# SCH_StairLights_2023-04-26.net
KiCad netlist of a schematic drawn in EasyEDA
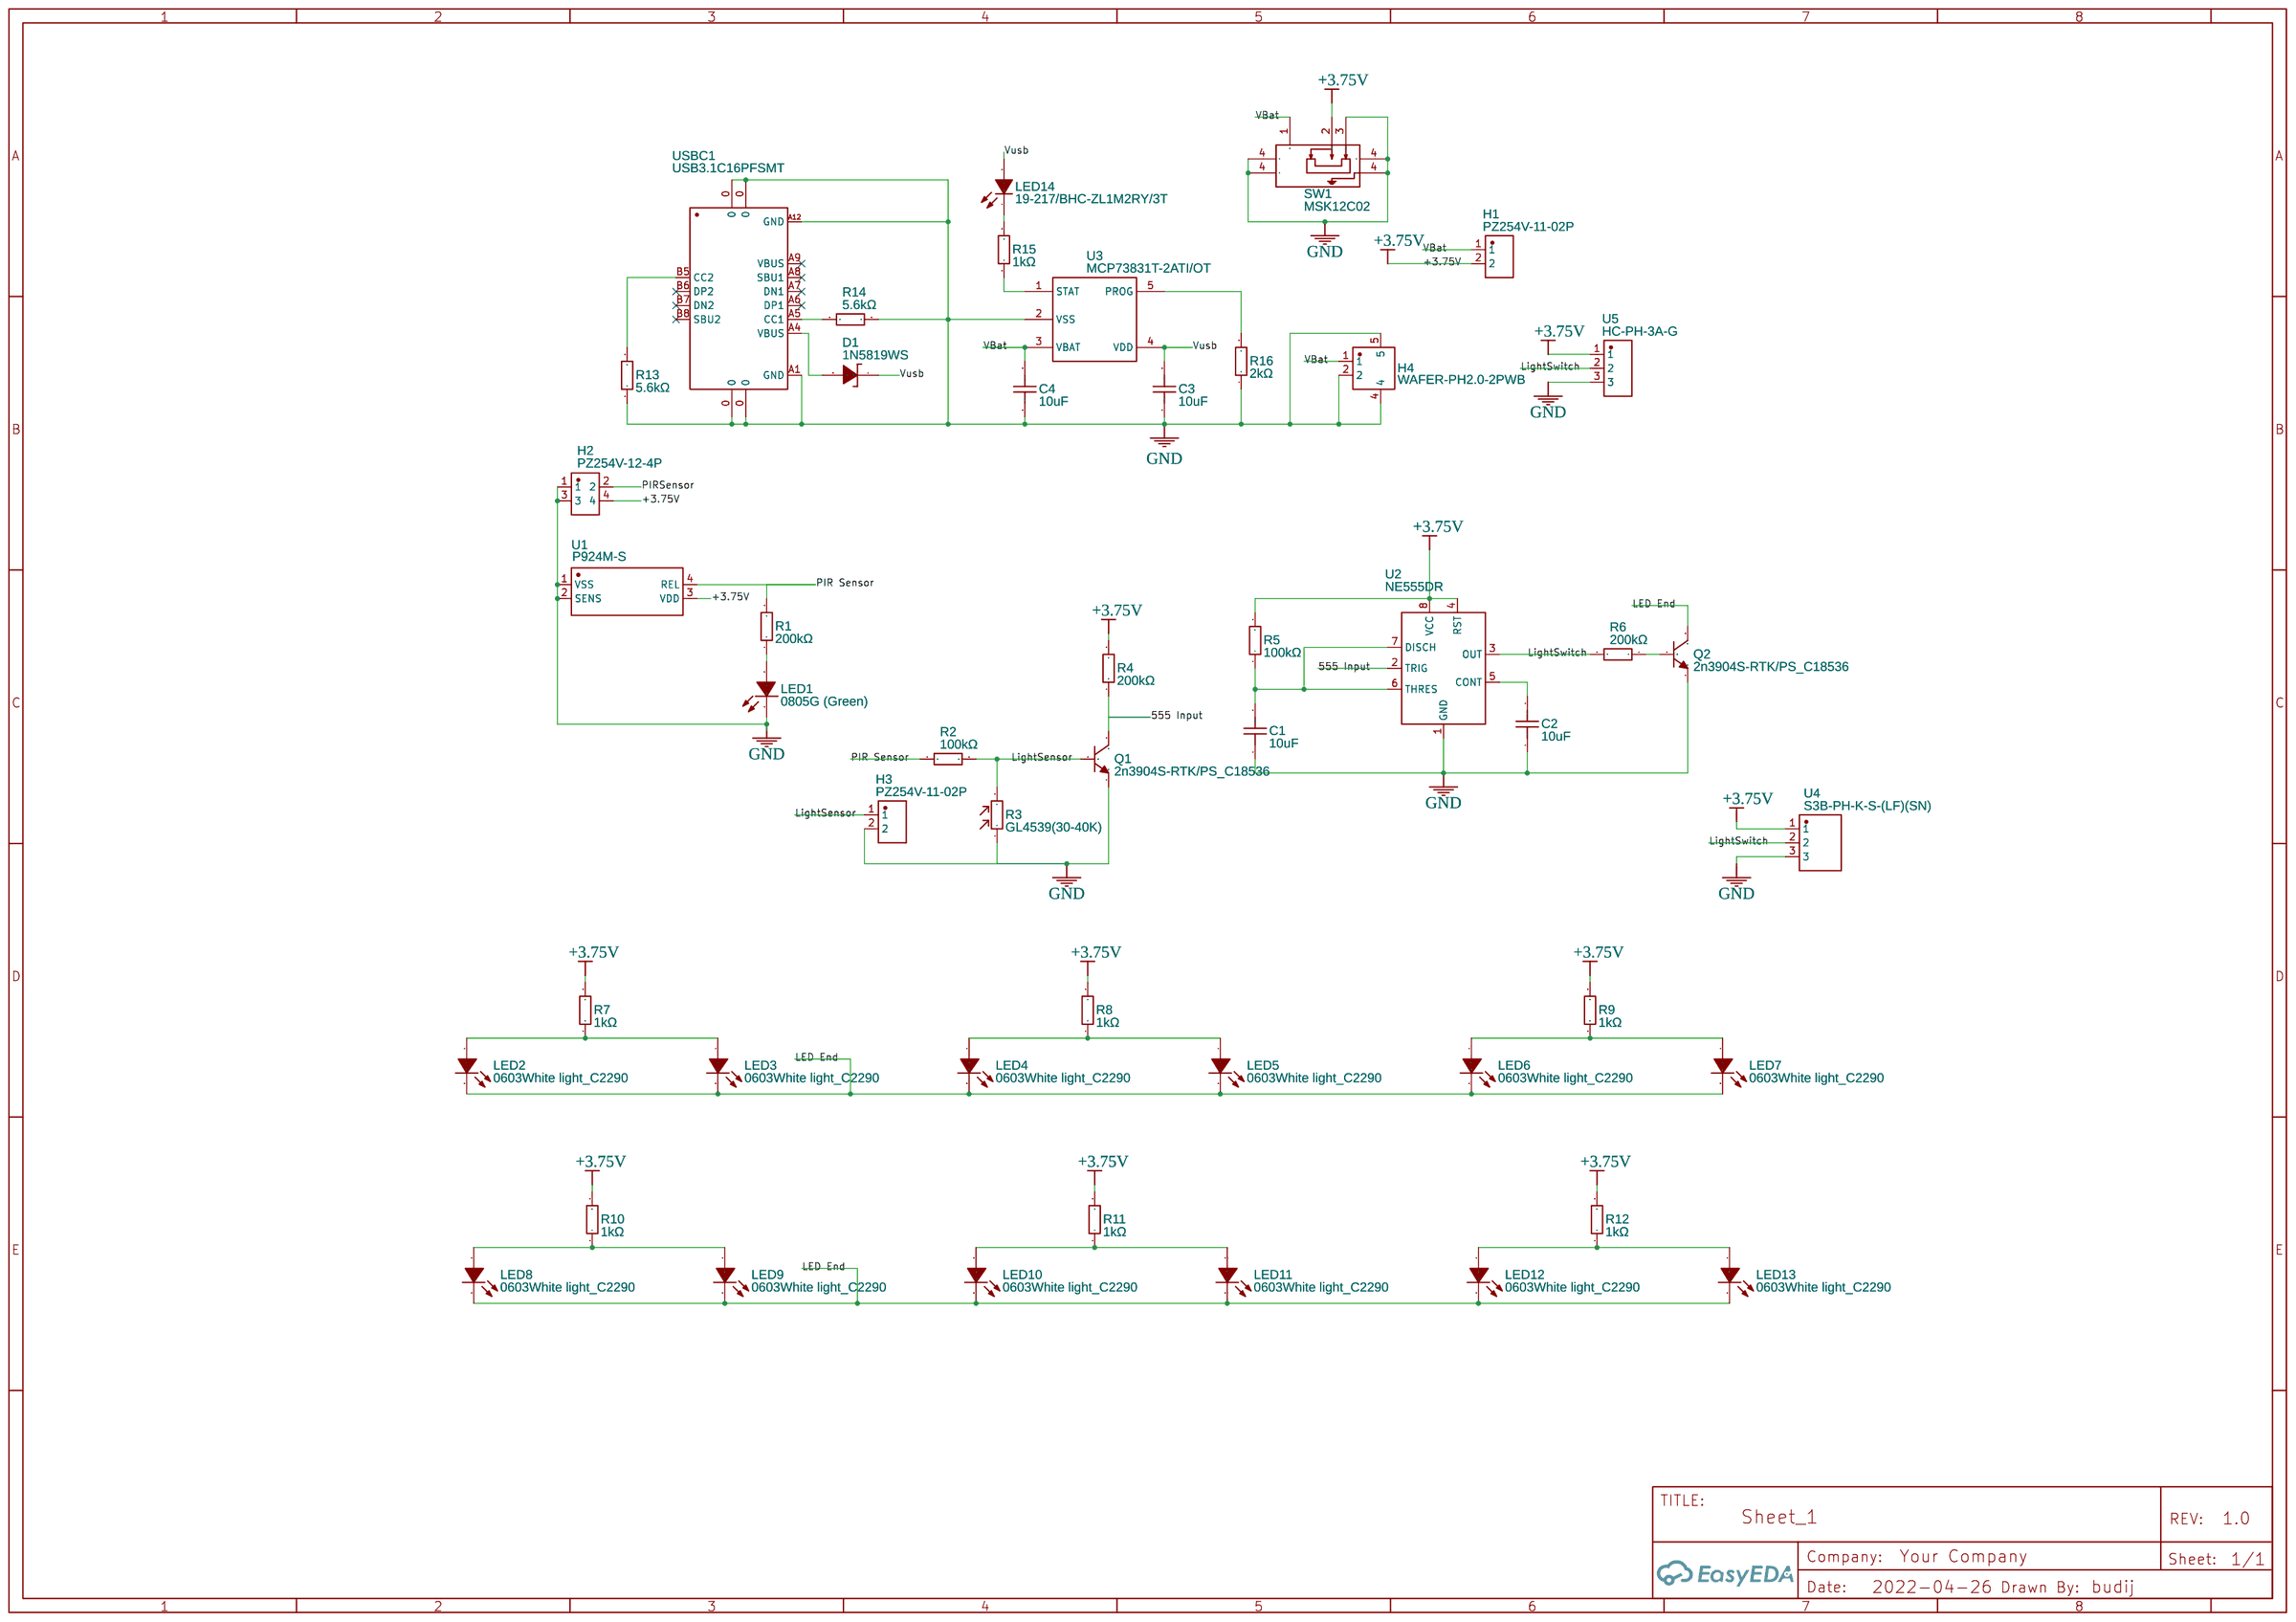
[diagram p0: schematic sheet]

(export (version "E")
  (design (tool "Eeschema 10.0.6"))
  (components
    (comp (ref "C1")
      (value "10uF")
      (fields
        (field (name "BOM_Manufacturer Part") "CL10A106KP8NNNC")
        (field (name "BOM_Supplier Part") "C19702")
      )
      (libsource (lib "") (part "CL10A106KP8NNNC"))
    )
    (comp (ref "C2")
      (value "10uF")
      (fields
        (field (name "BOM_Manufacturer Part") "CL10A106KP8NNNC")
        (field (name "BOM_Supplier Part") "C19702")
      )
      (libsource (lib "") (part "CL10A106KP8NNNC"))
    )
    (comp (ref "C3")
      (value "10uF")
      (fields
        (field (name "BOM_Manufacturer Part") "CL10A106KP8NNNC")
        (field (name "BOM_Supplier Part") "C19702")
      )
      (libsource (lib "") (part "CL10A106KP8NNNC"))
    )
    (comp (ref "C4")
      (value "10uF")
      (fields
        (field (name "BOM_Manufacturer Part") "CL10A106KP8NNNC")
        (field (name "BOM_Supplier Part") "C19702")
      )
      (libsource (lib "") (part "CL10A106KP8NNNC"))
    )
    (comp (ref "D1")
      (value "1N5819WS")
      (fields (field (name "BOM_Supplier Part") "C191023"))
      (libsource (lib "") (part "1N5819WS"))
    )
    (comp (ref "H1")
      (value "PZ254V-11-02P")
      (fields (field (name "BOM_Supplier Part") "C492401"))
      (libsource (lib "") (part "PZ254V-11-02P"))
    )
    (comp (ref "H2")
      (value "PZ254V-12-4P")
      (fields (field (name "BOM_Supplier Part") "C492419"))
      (libsource (lib "") (part "PZ254V-12-4P"))
    )
    (comp (ref "H3")
      (value "PZ254V-11-02P")
      (fields (field (name "BOM_Supplier Part") "C492401"))
      (libsource (lib "") (part "PZ254V-11-02P"))
    )
    (comp (ref "H4")
      (value "WAFER-PH2.0-2PWB")
      (fields (field (name "BOM_Supplier Part") "C3029440"))
      (libsource (lib "") (part "WAFER-PH2.0-2PWB"))
    )
    (comp (ref "LED1")
      (value "0805G (Green)")
      (fields (field (name "BOM_Supplier Part") "C2297"))
      (libsource (lib "") (part "0805G (Green)"))
    )
    (comp (ref "LED2")
      (value "0603White light_C2290")
      (fields (field (name "BOM_Manufacturer Part") "KT-0603白灯") (field (name "BOM_Supplier Part") "C2290"))
      (libsource (lib "") (part "0603White light_C2290"))
    )
    (comp (ref "LED3")
      (value "0603White light_C2290")
      (fields (field (name "BOM_Manufacturer Part") "KT-0603白灯") (field (name "BOM_Supplier Part") "C2290"))
      (libsource (lib "") (part "0603White light_C2290"))
    )
    (comp (ref "LED4")
      (value "0603White light_C2290")
      (fields (field (name "BOM_Manufacturer Part") "KT-0603白灯") (field (name "BOM_Supplier Part") "C2290"))
      (libsource (lib "") (part "0603White light_C2290"))
    )
    (comp (ref "LED5")
      (value "0603White light_C2290")
      (fields (field (name "BOM_Manufacturer Part") "KT-0603白灯") (field (name "BOM_Supplier Part") "C2290"))
      (libsource (lib "") (part "0603White light_C2290"))
    )
    (comp (ref "LED6")
      (value "0603White light_C2290")
      (fields (field (name "BOM_Manufacturer Part") "KT-0603白灯") (field (name "BOM_Supplier Part") "C2290"))
      (libsource (lib "") (part "0603White light_C2290"))
    )
    (comp (ref "LED7")
      (value "0603White light_C2290")
      (fields (field (name "BOM_Manufacturer Part") "KT-0603白灯") (field (name "BOM_Supplier Part") "C2290"))
      (libsource (lib "") (part "0603White light_C2290"))
    )
    (comp (ref "LED8")
      (value "0603White light_C2290")
      (fields (field (name "BOM_Manufacturer Part") "KT-0603白灯") (field (name "BOM_Supplier Part") "C2290"))
      (libsource (lib "") (part "0603White light_C2290"))
    )
    (comp (ref "LED9")
      (value "0603White light_C2290")
      (fields (field (name "BOM_Manufacturer Part") "KT-0603白灯") (field (name "BOM_Supplier Part") "C2290"))
      (libsource (lib "") (part "0603White light_C2290"))
    )
    (comp (ref "LED10")
      (value "0603White light_C2290")
      (fields (field (name "BOM_Manufacturer Part") "KT-0603白灯") (field (name "BOM_Supplier Part") "C2290"))
      (libsource (lib "") (part "0603White light_C2290"))
    )
    (comp (ref "LED11")
      (value "0603White light_C2290")
      (fields (field (name "BOM_Manufacturer Part") "KT-0603白灯") (field (name "BOM_Supplier Part") "C2290"))
      (libsource (lib "") (part "0603White light_C2290"))
    )
    (comp (ref "LED12")
      (value "0603White light_C2290")
      (fields (field (name "BOM_Manufacturer Part") "KT-0603白灯") (field (name "BOM_Supplier Part") "C2290"))
      (libsource (lib "") (part "0603White light_C2290"))
    )
    (comp (ref "LED13")
      (value "0603White light_C2290")
      (fields (field (name "BOM_Manufacturer Part") "KT-0603白灯") (field (name "BOM_Supplier Part") "C2290"))
      (libsource (lib "") (part "0603White light_C2290"))
    )
    (comp (ref "LED14")
      (value "19-217/BHC-ZL1M2RY/3T")
      (fields (field (name "BOM_Supplier Part") "C72041"))
      (libsource (lib "") (part "19-217/BHC-ZL1M2RY/3T"))
    )
    (comp (ref "Q1")
      (value "2n3904S-RTK/PS_C18536")
      (fields
        (field (name "BOM_Manufacturer Part") "2n3904S-RTK/PS")
        (field (name "BOM_Supplier Part") "C18536")
      )
      (libsource (lib "") (part "2n3904S-RTK/PS_C18536"))
    )
    (comp (ref "Q2")
      (value "2n3904S-RTK/PS_C18536")
      (fields
        (field (name "BOM_Manufacturer Part") "2n3904S-RTK/PS")
        (field (name "BOM_Supplier Part") "C18536")
      )
      (libsource (lib "") (part "2n3904S-RTK/PS_C18536"))
    )
    (comp (ref "R1")
      (value "200kΩ")
      (fields
        (field (name "BOM_Manufacturer Part") "0603WAF2003T5E")
        (field (name "BOM_Supplier Part") "C25811")
      )
      (libsource (lib "") (part "0603WAF2003T5E_1"))
    )
    (comp (ref "R2")
      (value "100kΩ")
      (fields
        (field (name "BOM_Manufacturer Part") "0603WAF1003T5E")
        (field (name "BOM_Supplier Part") "C25803")
      )
      (libsource (lib "") (part "0603WAF1003T5E_1"))
    )
    (comp (ref "R3")
      (value "GL4539(30-40K)")
      (fields (field (name "BOM_Supplier Part") "C11295"))
      (libsource (lib "") (part "GL4539(30-40K)"))
    )
    (comp (ref "R4")
      (value "200kΩ")
      (fields
        (field (name "BOM_Manufacturer Part") "0603WAF2003T5E")
        (field (name "BOM_Supplier Part") "C25811")
      )
      (libsource (lib "") (part "0603WAF2003T5E_1"))
    )
    (comp (ref "R5")
      (value "100kΩ")
      (fields
        (field (name "BOM_Manufacturer Part") "0603WAF1003T5E")
        (field (name "BOM_Supplier Part") "C25803")
      )
      (libsource (lib "") (part "0603WAF1003T5E"))
    )
    (comp (ref "R6")
      (value "200kΩ")
      (fields
        (field (name "BOM_Manufacturer Part") "0603WAF2003T5E")
        (field (name "BOM_Supplier Part") "C25811")
      )
      (libsource (lib "") (part "0603WAF2003T5E"))
    )
    (comp (ref "R7")
      (value "1kΩ")
      (fields
        (field (name "BOM_Manufacturer Part") "0603WAF1001T5E")
        (field (name "BOM_Supplier Part") "C21190")
      )
      (libsource (lib "") (part "0603WAF1001T5E"))
    )
    (comp (ref "R8")
      (value "1kΩ")
      (fields
        (field (name "BOM_Manufacturer Part") "0603WAF1001T5E")
        (field (name "BOM_Supplier Part") "C21190")
      )
      (libsource (lib "") (part "0603WAF1001T5E"))
    )
    (comp (ref "R9")
      (value "1kΩ")
      (fields
        (field (name "BOM_Manufacturer Part") "0603WAF1001T5E")
        (field (name "BOM_Supplier Part") "C21190")
      )
      (libsource (lib "") (part "0603WAF1001T5E"))
    )
    (comp (ref "R10")
      (value "1kΩ")
      (fields
        (field (name "BOM_Manufacturer Part") "0603WAF1001T5E")
        (field (name "BOM_Supplier Part") "C21190")
      )
      (libsource (lib "") (part "0603WAF1001T5E"))
    )
    (comp (ref "R11")
      (value "1kΩ")
      (fields
        (field (name "BOM_Manufacturer Part") "0603WAF1001T5E")
        (field (name "BOM_Supplier Part") "C21190")
      )
      (libsource (lib "") (part "0603WAF1001T5E"))
    )
    (comp (ref "R12")
      (value "1kΩ")
      (fields
        (field (name "BOM_Manufacturer Part") "0603WAF1001T5E")
        (field (name "BOM_Supplier Part") "C21190")
      )
      (libsource (lib "") (part "0603WAF1001T5E"))
    )
    (comp (ref "R13")
      (value "5.6kΩ")
      (fields
        (field (name "BOM_Manufacturer Part") "0603WAF5601T5E")
        (field (name "BOM_Supplier Part") "C23189")
      )
      (libsource (lib "") (part "0603WAF5601T5E"))
    )
    (comp (ref "R14")
      (value "5.6kΩ")
      (fields
        (field (name "BOM_Manufacturer Part") "0603WAF5601T5E")
        (field (name "BOM_Supplier Part") "C23189")
      )
      (libsource (lib "") (part "0603WAF5601T5E_1"))
    )
    (comp (ref "R15")
      (value "1kΩ")
      (fields
        (field (name "BOM_Manufacturer Part") "0603WAF1001T5E")
        (field (name "BOM_Supplier Part") "C21190")
      )
      (libsource (lib "") (part "0603WAF1001T5E"))
    )
    (comp (ref "R16")
      (value "2kΩ")
      (fields
        (field (name "BOM_Manufacturer Part") "0603WAF2001T5E")
        (field (name "BOM_Supplier Part") "C22975")
      )
      (libsource (lib "") (part "0603WAF2001T5E"))
    )
    (comp (ref "SW1")
      (value "MSK12C02")
      (fields (field (name "BOM_Supplier Part") "C431540"))
      (libsource (lib "") (part "MSK12C02"))
    )
    (comp (ref "U1")
      (value "P924M-S")
      (fields (field (name "BOM_Supplier Part") "C139580"))
      (libsource (lib "") (part "P924M-S"))
    )
    (comp (ref "U2")
      (value "NE555DR")
      (fields (field (name "BOM_Supplier Part") "C7593"))
      (libsource (lib "") (part "NE555DR"))
    )
    (comp (ref "U3")
      (value "MCP73831T-2ATI/OT")
      (fields (field (name "BOM_Supplier Part") "C14879"))
      (libsource (lib "") (part "MCP73831T-2ATI/OT"))
    )
    (comp (ref "U4")
      (value "S3B-PH-K-S-(LF)(SN)")
      (fields
        (field (name "BOM_Manufacturer Part") "S3B-PH-K-S(LF)(SN)")
        (field (name "BOM_Supplier Part") "C157929")
      )
      (libsource (lib "") (part "S3B-PH-K-S-(LF)(SN)"))
    )
    (comp (ref "U5")
      (value "HC-PH-3A-G")
      (fields (field (name "BOM_Supplier Part") "C5342436"))
      (libsource (lib "") (part "HC-PH-3A-G"))
    )
    (comp (ref "USBC1")
      (value "USB3.1C16PFSMT")
      (fields (field (name "BOM_Supplier Part") "C167321"))
      (libsource (lib "") (part "USB3.1C16PFSMT"))
    )
  )
  (nets
    (net (code "1") (name "+3.75V") (class "Default")
      (node (ref "H1") (pin "2") (pinfunction "2_2") (pintype "unspecified"))
      (node (ref "H2") (pin "4") (pinfunction "4_4") (pintype "unspecified"))
      (node (ref "R10") (pin "2") (pinfunction "2_2") (pintype "input"))
      (node (ref "R11") (pin "2") (pinfunction "2_2") (pintype "input"))
      (node (ref "R12") (pin "2") (pinfunction "2_2") (pintype "input"))
      (node (ref "R4") (pin "2") (pinfunction "2_2") (pintype "input"))
      (node (ref "R5") (pin "2") (pinfunction "2_2") (pintype "input"))
      (node (ref "R7") (pin "2") (pinfunction "2_2") (pintype "input"))
      (node (ref "R8") (pin "2") (pinfunction "2_2") (pintype "input"))
      (node (ref "R9") (pin "2") (pinfunction "2_2") (pintype "input"))
      (node (ref "SW1") (pin "2") (pinfunction "2_2") (pintype "unspecified"))
      (node (ref "U1") (pin "3") (pinfunction "VDD_3") (pintype "unspecified"))
      (node (ref "U2") (pin "4") (pinfunction "RST_4") (pintype "unspecified"))
      (node (ref "U2") (pin "8") (pinfunction "VCC_8") (pintype "unspecified"))
      (node (ref "U4") (pin "1") (pinfunction "1_1") (pintype "unspecified"))
      (node (ref "U5") (pin "1") (pinfunction "1_1") (pintype "unspecified"))
    )
    (net (code "2") (name "/555 Input") (class "Default")
      (node (ref "Q1") (pin "3") (pinfunction "C_3") (pintype "input"))
      (node (ref "R4") (pin "1") (pinfunction "1_1") (pintype "input"))
      (node (ref "U2") (pin "2") (pinfunction "TRIG_2") (pintype "unspecified"))
    )
    (net (code "3") (name "/LED End") (class "Default")
      (node (ref "LED10") (pin "2") (pinfunction "K_2") (pintype "unspecified"))
      (node (ref "LED11") (pin "2") (pinfunction "K_2") (pintype "unspecified"))
      (node (ref "LED12") (pin "2") (pinfunction "K_2") (pintype "unspecified"))
      (node (ref "LED13") (pin "2") (pinfunction "K_2") (pintype "unspecified"))
      (node (ref "LED2") (pin "2") (pinfunction "K_2") (pintype "unspecified"))
      (node (ref "LED3") (pin "2") (pinfunction "K_2") (pintype "unspecified"))
      (node (ref "LED4") (pin "2") (pinfunction "K_2") (pintype "unspecified"))
      (node (ref "LED5") (pin "2") (pinfunction "K_2") (pintype "unspecified"))
      (node (ref "LED6") (pin "2") (pinfunction "K_2") (pintype "unspecified"))
      (node (ref "LED7") (pin "2") (pinfunction "K_2") (pintype "unspecified"))
      (node (ref "LED8") (pin "2") (pinfunction "K_2") (pintype "unspecified"))
      (node (ref "LED9") (pin "2") (pinfunction "K_2") (pintype "unspecified"))
      (node (ref "Q2") (pin "3") (pinfunction "C_3") (pintype "input"))
    )
    (net (code "4") (name "/LightSensor") (class "Default")
      (node (ref "H3") (pin "1") (pinfunction "1_1") (pintype "unspecified"))
      (node (ref "Q1") (pin "2") (pinfunction "B_2") (pintype "input"))
      (node (ref "R2") (pin "2") (pinfunction "2_2") (pintype "input"))
      (node (ref "R3") (pin "2") (pinfunction "2_2") (pintype "input"))
    )
    (net (code "5") (name "/LightSwitch") (class "Default")
      (node (ref "R6") (pin "2") (pinfunction "2_2") (pintype "input"))
      (node (ref "U2") (pin "3") (pinfunction "OUT_3") (pintype "unspecified"))
      (node (ref "U4") (pin "2") (pinfunction "2_2") (pintype "unspecified"))
      (node (ref "U5") (pin "2") (pinfunction "2_2") (pintype "unspecified"))
    )
    (net (code "6") (name "/PIR Sensor") (class "Default")
      (node (ref "R1") (pin "2") (pinfunction "2_2") (pintype "input"))
      (node (ref "R2") (pin "1") (pinfunction "1_1") (pintype "input"))
      (node (ref "U1") (pin "4") (pinfunction "REL_4") (pintype "unspecified"))
    )
    (net (code "7") (name "/PIRSensor") (class "Default")
      (node (ref "H2") (pin "2") (pinfunction "2_2") (pintype "unspecified"))
    )
    (net (code "8") (name "/VBat") (class "Default")
      (node (ref "C4") (pin "2") (pinfunction "2_2") (pintype "unspecified"))
      (node (ref "H1") (pin "1") (pinfunction "1_1") (pintype "unspecified"))
      (node (ref "H4") (pin "1") (pinfunction "1_1") (pintype "unspecified"))
      (node (ref "SW1") (pin "1") (pinfunction "1_1") (pintype "unspecified"))
      (node (ref "U3") (pin "3") (pinfunction "VBAT_3") (pintype "unspecified"))
    )
    (net (code "9") (name "/Vusb") (class "Default")
      (node (ref "C3") (pin "2") (pinfunction "2_2") (pintype "unspecified"))
      (node (ref "D1") (pin "1") (pinfunction "C_1") (pintype "unspecified"))
      (node (ref "LED14") (pin "2") (pinfunction "A_2") (pintype "input"))
      (node (ref "U3") (pin "4") (pinfunction "VDD_4") (pintype "unspecified"))
    )
    (net (code "10") (name "GND") (class "Default")
      (node (ref "C1") (pin "1") (pinfunction "1_1") (pintype "unspecified"))
      (node (ref "C2") (pin "1") (pinfunction "1_1") (pintype "unspecified"))
      (node (ref "C3") (pin "1") (pinfunction "1_1") (pintype "unspecified"))
      (node (ref "C4") (pin "1") (pinfunction "1_1") (pintype "unspecified"))
      (node (ref "H2") (pin "1") (pinfunction "1_1") (pintype "unspecified"))
      (node (ref "H2") (pin "3") (pinfunction "3_3") (pintype "unspecified"))
      (node (ref "H3") (pin "2") (pinfunction "2_2") (pintype "unspecified"))
      (node (ref "H4") (pin "2") (pinfunction "2_2") (pintype "unspecified"))
      (node (ref "H4") (pin "4") (pinfunction "4_4") (pintype "unspecified"))
      (node (ref "H4") (pin "5") (pinfunction "5_5") (pintype "unspecified"))
      (node (ref "LED1") (pin "1") (pinfunction "K_1") (pintype "unspecified"))
      (node (ref "Q1") (pin "1") (pinfunction "E_1") (pintype "input"))
      (node (ref "Q2") (pin "1") (pinfunction "E_1") (pintype "input"))
      (node (ref "R13") (pin "1") (pinfunction "1_1") (pintype "input"))
      (node (ref "R14") (pin "2") (pinfunction "2_2") (pintype "input"))
      (node (ref "R16") (pin "1") (pinfunction "1_1") (pintype "input"))
      (node (ref "R3") (pin "1") (pinfunction "1_1") (pintype "input"))
      (node (ref "SW1") (pin "3") (pinfunction "3_3") (pintype "unspecified"))
      (node (ref "SW1") (pin "4") (pinfunction "4_4") (pintype "unspecified"))
      (node (ref "U1") (pin "1") (pinfunction "VSS_1") (pintype "unspecified"))
      (node (ref "U1") (pin "2") (pinfunction "SENS_2") (pintype "unspecified"))
      (node (ref "U2") (pin "1") (pinfunction "GND_1") (pintype "unspecified"))
      (node (ref "U3") (pin "2") (pinfunction "VSS_2") (pintype "unspecified"))
      (node (ref "U4") (pin "3") (pinfunction "3_3") (pintype "unspecified"))
      (node (ref "U5") (pin "3") (pinfunction "3_3") (pintype "unspecified"))
      (node (ref "USBC1") (pin "0") (pinfunction "0_0") (pintype "unspecified"))
      (node (ref "USBC1") (pin "A1") (pinfunction "GND_A1") (pintype "unspecified"))
      (node (ref "USBC1") (pin "A12") (pinfunction "GND_A12") (pintype "unspecified"))
    )
    (net (code "11") (name "Net-(D1-A)") (class "Default")
      (node (ref "D1") (pin "2") (pinfunction "A_2") (pintype "unspecified"))
      (node (ref "USBC1") (pin "A4") (pinfunction "VBUS_A4") (pintype "unspecified"))
    )
    (net (code "12") (name "Net-(LED1-A)") (class "Default")
      (node (ref "LED1") (pin "2") (pinfunction "A_2") (pintype "unspecified"))
      (node (ref "R1") (pin "1") (pinfunction "1_1") (pintype "input"))
    )
    (net (code "13") (name "Net-(LED2-A)") (class "Default")
      (node (ref "LED2") (pin "1") (pinfunction "A_1") (pintype "unspecified"))
      (node (ref "LED3") (pin "1") (pinfunction "A_1") (pintype "unspecified"))
      (node (ref "R7") (pin "1") (pinfunction "1_1") (pintype "input"))
    )
    (net (code "14") (name "Net-(LED4-A)") (class "Default")
      (node (ref "LED4") (pin "1") (pinfunction "A_1") (pintype "unspecified"))
      (node (ref "LED5") (pin "1") (pinfunction "A_1") (pintype "unspecified"))
      (node (ref "R8") (pin "1") (pinfunction "1_1") (pintype "input"))
    )
    (net (code "15") (name "Net-(LED6-A)") (class "Default")
      (node (ref "LED6") (pin "1") (pinfunction "A_1") (pintype "unspecified"))
      (node (ref "LED7") (pin "1") (pinfunction "A_1") (pintype "unspecified"))
      (node (ref "R9") (pin "1") (pinfunction "1_1") (pintype "input"))
    )
    (net (code "16") (name "Net-(LED8-A)") (class "Default")
      (node (ref "LED8") (pin "1") (pinfunction "A_1") (pintype "unspecified"))
      (node (ref "LED9") (pin "1") (pinfunction "A_1") (pintype "unspecified"))
      (node (ref "R10") (pin "1") (pinfunction "1_1") (pintype "input"))
    )
    (net (code "17") (name "Net-(LED10-A)") (class "Default")
      (node (ref "LED10") (pin "1") (pinfunction "A_1") (pintype "unspecified"))
      (node (ref "LED11") (pin "1") (pinfunction "A_1") (pintype "unspecified"))
      (node (ref "R11") (pin "1") (pinfunction "1_1") (pintype "input"))
    )
    (net (code "18") (name "Net-(LED12-A)") (class "Default")
      (node (ref "LED12") (pin "1") (pinfunction "A_1") (pintype "unspecified"))
      (node (ref "LED13") (pin "1") (pinfunction "A_1") (pintype "unspecified"))
      (node (ref "R12") (pin "1") (pinfunction "1_1") (pintype "input"))
    )
    (net (code "19") (name "Net-(LED14-C)") (class "Default")
      (node (ref "LED14") (pin "1") (pinfunction "C_1") (pintype "input"))
      (node (ref "R15") (pin "2") (pinfunction "2_2") (pintype "input"))
    )
    (net (code "20") (name "Net-(Q2-B)") (class "Default")
      (node (ref "Q2") (pin "2") (pinfunction "B_2") (pintype "input"))
      (node (ref "R6") (pin "1") (pinfunction "1_1") (pintype "input"))
    )
    (net (code "21") (name "Net-(U2-CONT)") (class "Default")
      (node (ref "C2") (pin "2") (pinfunction "2_2") (pintype "unspecified"))
      (node (ref "U2") (pin "5") (pinfunction "CONT_5") (pintype "unspecified"))
    )
    (net (code "22") (name "Net-(U2-DISCH)") (class "Default")
      (node (ref "C1") (pin "2") (pinfunction "2_2") (pintype "unspecified"))
      (node (ref "R5") (pin "1") (pinfunction "1_1") (pintype "input"))
      (node (ref "U2") (pin "6") (pinfunction "THRES_6") (pintype "unspecified"))
      (node (ref "U2") (pin "7") (pinfunction "DISCH_7") (pintype "unspecified"))
    )
    (net (code "23") (name "Net-(U3-PROG)") (class "Default")
      (node (ref "R16") (pin "2") (pinfunction "2_2") (pintype "input"))
      (node (ref "U3") (pin "5") (pinfunction "PROG_5") (pintype "unspecified"))
    )
    (net (code "24") (name "Net-(U3-STAT)") (class "Default")
      (node (ref "R15") (pin "1") (pinfunction "1_1") (pintype "input"))
      (node (ref "U3") (pin "1") (pinfunction "STAT_1") (pintype "unspecified"))
    )
    (net (code "25") (name "Net-(USBC1-CC1)") (class "Default")
      (node (ref "R14") (pin "1") (pinfunction "1_1") (pintype "input"))
      (node (ref "USBC1") (pin "A5") (pinfunction "CC1_A5") (pintype "unspecified"))
    )
    (net (code "26") (name "Net-(USBC1-CC2)") (class "Default")
      (node (ref "R13") (pin "2") (pinfunction "2_2") (pintype "input"))
      (node (ref "USBC1") (pin "B5") (pinfunction "CC2_B5") (pintype "unspecified"))
    )
    (net (code "27") (name "unconnected-(USBC1-DN1-PadA7)") (class "Default")
      (node (ref "USBC1") (pin "A7") (pinfunction "DN1_A7") (pintype "unspecified+no_connect"))
    )
    (net (code "28") (name "unconnected-(USBC1-DN2-PadB7)") (class "Default")
      (node (ref "USBC1") (pin "B7") (pinfunction "DN2_B7") (pintype "unspecified+no_connect"))
    )
    (net (code "29") (name "unconnected-(USBC1-DP1-PadA6)") (class "Default")
      (node (ref "USBC1") (pin "A6") (pinfunction "DP1_A6") (pintype "unspecified+no_connect"))
    )
    (net (code "30") (name "unconnected-(USBC1-DP2-PadB6)") (class "Default")
      (node (ref "USBC1") (pin "B6") (pinfunction "DP2_B6") (pintype "unspecified+no_connect"))
    )
    (net (code "31") (name "unconnected-(USBC1-SBU1-PadA8)") (class "Default")
      (node (ref "USBC1") (pin "A8") (pinfunction "SBU1_A8") (pintype "unspecified+no_connect"))
    )
    (net (code "32") (name "unconnected-(USBC1-SBU2-PadB8)") (class "Default")
      (node (ref "USBC1") (pin "B8") (pinfunction "SBU2_B8") (pintype "unspecified+no_connect"))
    )
    (net (code "33") (name "unconnected-(USBC1-VBUS-PadA9)") (class "Default")
      (node (ref "USBC1") (pin "A9") (pinfunction "VBUS_A9") (pintype "unspecified+no_connect"))
    )
  )
)
